# battery_charger_li-ion.net
KiCad netlist of a schematic drawn in Altium Designer
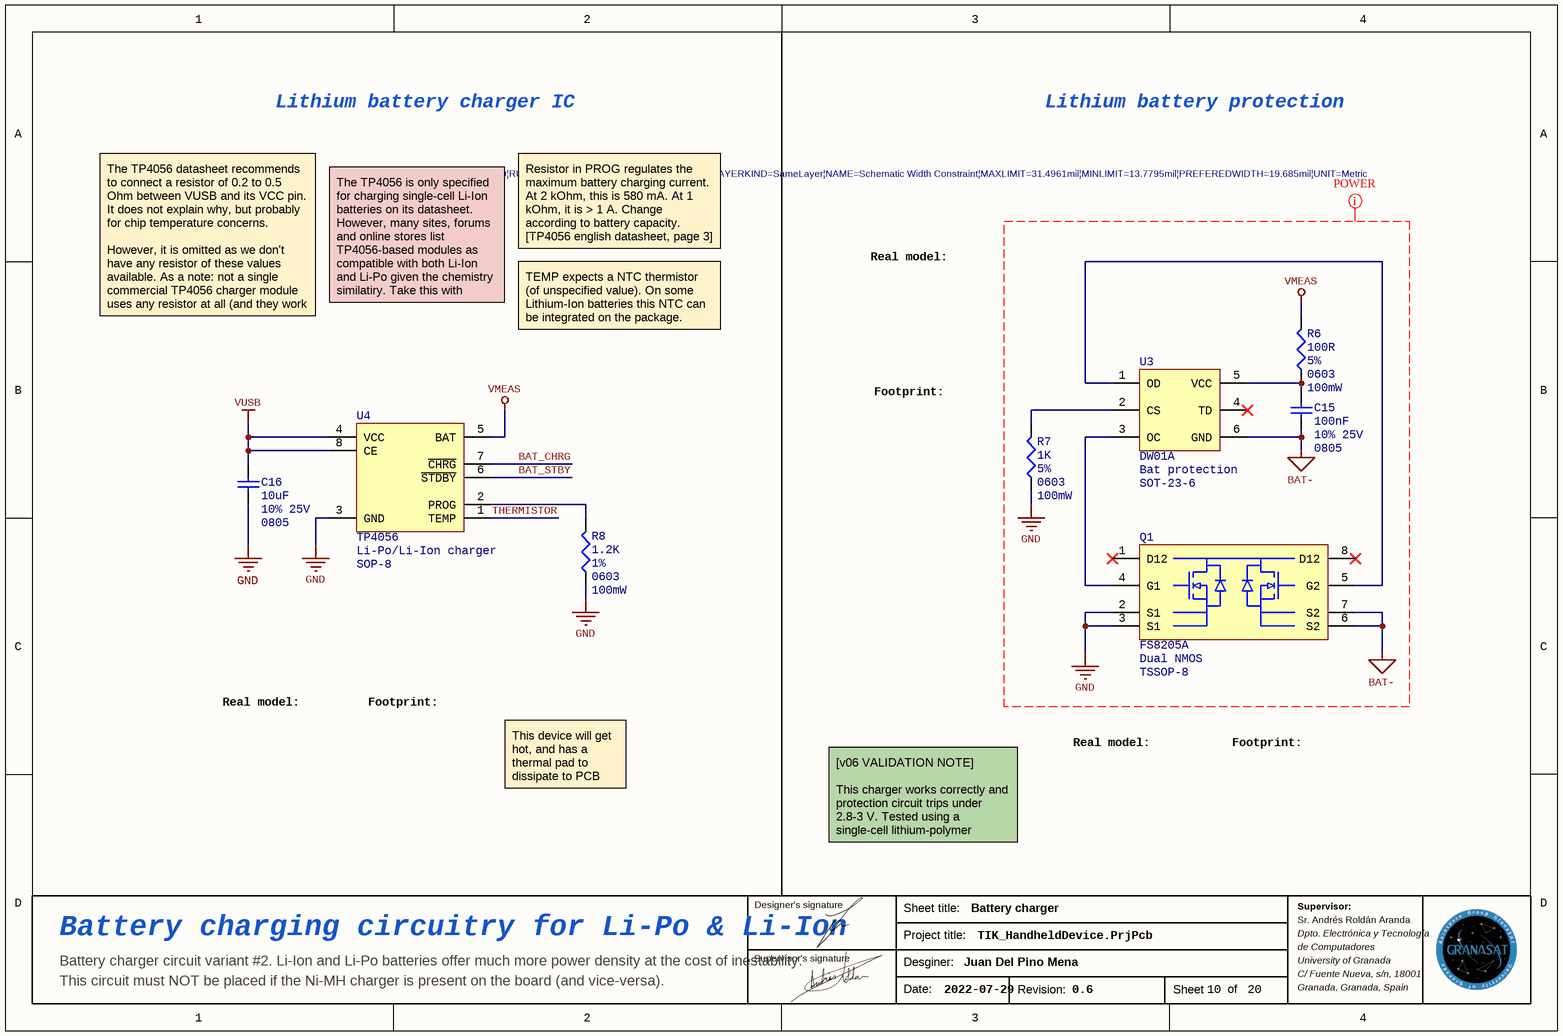
[diagram p0: battery_charger_li-ion.SchDoc]

(export (version "E")
  (design (tool "Eeschema 10.0.6"))
  (components
    (comp (ref "C15")
      (value "100nF")
      (footprint "CAP 0805_2012")
      (description "Ceramic cap size 0805")
      (fields
        (field (name "TOLERANCE") "10% 25V")
        (field (name "PACKAGEDESCRIPTION") "0805")
        (field (name "Comment") "Cap_cer_0805")
      )
      (libsource (lib "tik_handheld_schlib") (part "Cap_cer_0805_100nF_10%"))
    )
    (comp (ref "C16")
      (value "10uF")
      (footprint "CAP 0805_2012")
      (description "Ceramic cap size 0805")
      (fields
        (field (name "TOLERANCE") "10% 25V")
        (field (name "PACKAGEDESCRIPTION") "0805")
        (field (name "Comment") "Cap_cer_0805")
      )
      (libsource (lib "tik_handheld_schlib") (part "Cap_cer_0805_10uF_10%"))
    )
    (comp (ref "Q1")
      (value "FS8205A")
      (footprint "TSSOP-8 FS8205A")
      (description "Dual N-channel Enhancement mode power MOSFET")
      (fields
        (field (name "PART") "FS8205A")
        (field (name "TYPE") "Dual NMOS")
        (field (name "PACKAGEDESCRIPTION") "TSSOP-8")
      )
      (libsource (lib "tik_handheld_schlib") (part "IC FS8205A Dual NMOS"))
    )
    (comp (ref "R6")
      (value "100R")
      (footprint "RES 0603_1608")
      (description "Res size 0603 SMD mounting, low power")
      (fields
        (field (name "TOLERANCE") "5%")
        (field (name "PACKAGEDESCRIPTION") "0603")
        (field (name "POWERDISIPATED") "100mW")
        (field (name "Comment") "Res_0603_100R_5%_100mW")
      )
      (libsource (lib "tik_handheld_schlib") (part "Res_0603_100R_5%_100mW"))
    )
    (comp (ref "R7")
      (value "1K")
      (footprint "RES 0603_1608")
      (description "Res size 0603 SMD mounting, low power")
      (fields
        (field (name "TOLERANCE") "5%")
        (field (name "PACKAGEDESCRIPTION") "0603")
        (field (name "POWERDISIPATED") "100mW")
        (field (name "Comment") "Res_0603_1K_5%_100mW")
      )
      (libsource (lib "tik_handheld_schlib") (part "Res_0603_1K_5%_100mW"))
    )
    (comp (ref "R8")
      (value "1.2K")
      (footprint "RES 0603_1608")
      (description "Res size 0603 SMD mounting, low power")
      (fields
        (field (name "TOLERANCE") "1%")
        (field (name "PACKAGEDESCRIPTION") "0603")
        (field (name "POWERDISIPATED") "100mW")
        (field (name "Comment") "Res_0603_1.2K_1%_100mW")
      )
      (libsource (lib "tik_handheld_schlib") (part "Res_0603_1.2K_1%_100mW"))
    )
    (comp (ref "U3")
      (value "DW01A")
      (footprint "SOT-23-6 DW01A")
      (description "DW01A One cell Li-Po/Li-ion Battery protection IC")
      (fields
        (field (name "PART") "DW01A")
        (field (name "TYPE") "Bat protection")
        (field (name "PACKAGEDESCRIPTION") "SOT-23-6")
      )
      (libsource (lib "tik_handheld_schlib") (part "IC DW01A bat protection"))
    )
    (comp (ref "U4")
      (value "TP4056")
      (footprint "SOIC-8-D0008A TP4056")
      (description "1A Standalone Linear Li-lon Battery Charger with Thermal Regulation in SOP-8")
      (fields
        (field (name "PART") "TP4056")
        (field (name "TYPE") "Li-Po/Li-Ion charger")
        (field (name "PACKAGEDESCRIPTION") "SOP-8")
      )
      (libsource (lib "tik_handheld_schlib") (part "IC TP4056 BAT Charger"))
    )
  )
  (nets
    (net (code "1") (name "/BAT_CHRG") (class "Default")
      (node (ref "U4") (pin "7") (pinfunction "~{CHRG}_7") (pintype "open_collector"))
    )
    (net (code "2") (name "/BAT_STBY") (class "Default")
      (node (ref "U4") (pin "6") (pinfunction "~{STDBY}_6") (pintype "open_collector"))
    )
    (net (code "3") (name "/THERMISTOR") (class "Default")
      (node (ref "U4") (pin "1") (pinfunction "TEMP_1") (pintype "passive"))
    )
    (net (code "4") (name "BAT-") (class "Default")
      (node (ref "C15") (pin "1") (pinfunction "1_1") (pintype "passive"))
      (node (ref "Q1") (pin "6") (pinfunction "S2_6") (pintype "passive"))
      (node (ref "Q1") (pin "7") (pinfunction "S2_7") (pintype "passive"))
      (node (ref "U3") (pin "6") (pinfunction "GND_6") (pintype "power_in"))
    )
    (net (code "5") (name "GND") (class "Default")
      (node (ref "C16") (pin "1") (pinfunction "1_1") (pintype "passive"))
      (node (ref "Q1") (pin "2") (pinfunction "S1_2") (pintype "passive"))
      (node (ref "Q1") (pin "3") (pinfunction "S1_3") (pintype "passive"))
      (node (ref "R7") (pin "1") (pinfunction "1_1") (pintype "passive"))
      (node (ref "R8") (pin "1") (pinfunction "1_1") (pintype "passive"))
      (node (ref "U4") (pin "3") (pinfunction "GND_3") (pintype "power_in"))
    )
    (net (code "6") (name "Net-(Q1-G1)") (class "Default")
      (node (ref "Q1") (pin "4") (pinfunction "G1_4") (pintype "passive"))
      (node (ref "U3") (pin "3") (pinfunction "OC_3") (pintype "passive"))
    )
    (net (code "7") (name "Net-(Q1-G2)") (class "Default")
      (node (ref "Q1") (pin "5") (pinfunction "G2_5") (pintype "passive"))
      (node (ref "U3") (pin "1") (pinfunction "OD_1") (pintype "passive"))
    )
    (net (code "8") (name "Net-(U3-CS)") (class "Default")
      (node (ref "R7") (pin "2") (pinfunction "2_2") (pintype "passive"))
      (node (ref "U3") (pin "2") (pinfunction "CS_2") (pintype "passive"))
    )
    (net (code "9") (name "Net-(U3-VCC)") (class "Default")
      (node (ref "C15") (pin "2") (pinfunction "2_2") (pintype "passive"))
      (node (ref "R6") (pin "1") (pinfunction "1_1") (pintype "passive"))
      (node (ref "U3") (pin "5") (pinfunction "VCC_5") (pintype "power_in"))
    )
    (net (code "10") (name "Net-(U4-PROG)") (class "Default")
      (node (ref "R8") (pin "2") (pinfunction "2_2") (pintype "passive"))
      (node (ref "U4") (pin "2") (pinfunction "PROG_2") (pintype "passive"))
    )
    (net (code "11") (name "VMEAS") (class "Default")
      (node (ref "R6") (pin "2") (pinfunction "2_2") (pintype "passive"))
      (node (ref "U4") (pin "5") (pinfunction "BAT_5") (pintype "power_in"))
    )
    (net (code "12") (name "VUSB") (class "Default")
      (node (ref "C16") (pin "2") (pinfunction "2_2") (pintype "passive"))
      (node (ref "U4") (pin "4") (pinfunction "VCC_4") (pintype "power_in"))
      (node (ref "U4") (pin "8") (pinfunction "CE_8") (pintype "passive"))
    )
    (net (code "13") (name "unconnected-(Q1-D12-Pad1)") (class "Default")
      (node (ref "Q1") (pin "1") (pinfunction "D12_1") (pintype "passive+no_connect"))
    )
    (net (code "14") (name "unconnected-(Q1-D12-Pad8)") (class "Default")
      (node (ref "Q1") (pin "8") (pinfunction "D12_8") (pintype "passive+no_connect"))
    )
    (net (code "15") (name "unconnected-(U3-TD-Pad4)") (class "Default")
      (node (ref "U3") (pin "4") (pinfunction "TD_4") (pintype "passive+no_connect"))
    )
  )
)
